# HLK_RM60_KIT_RJ45_V1_1.net
KiCad netlist of a schematic drawn in Altium Designer
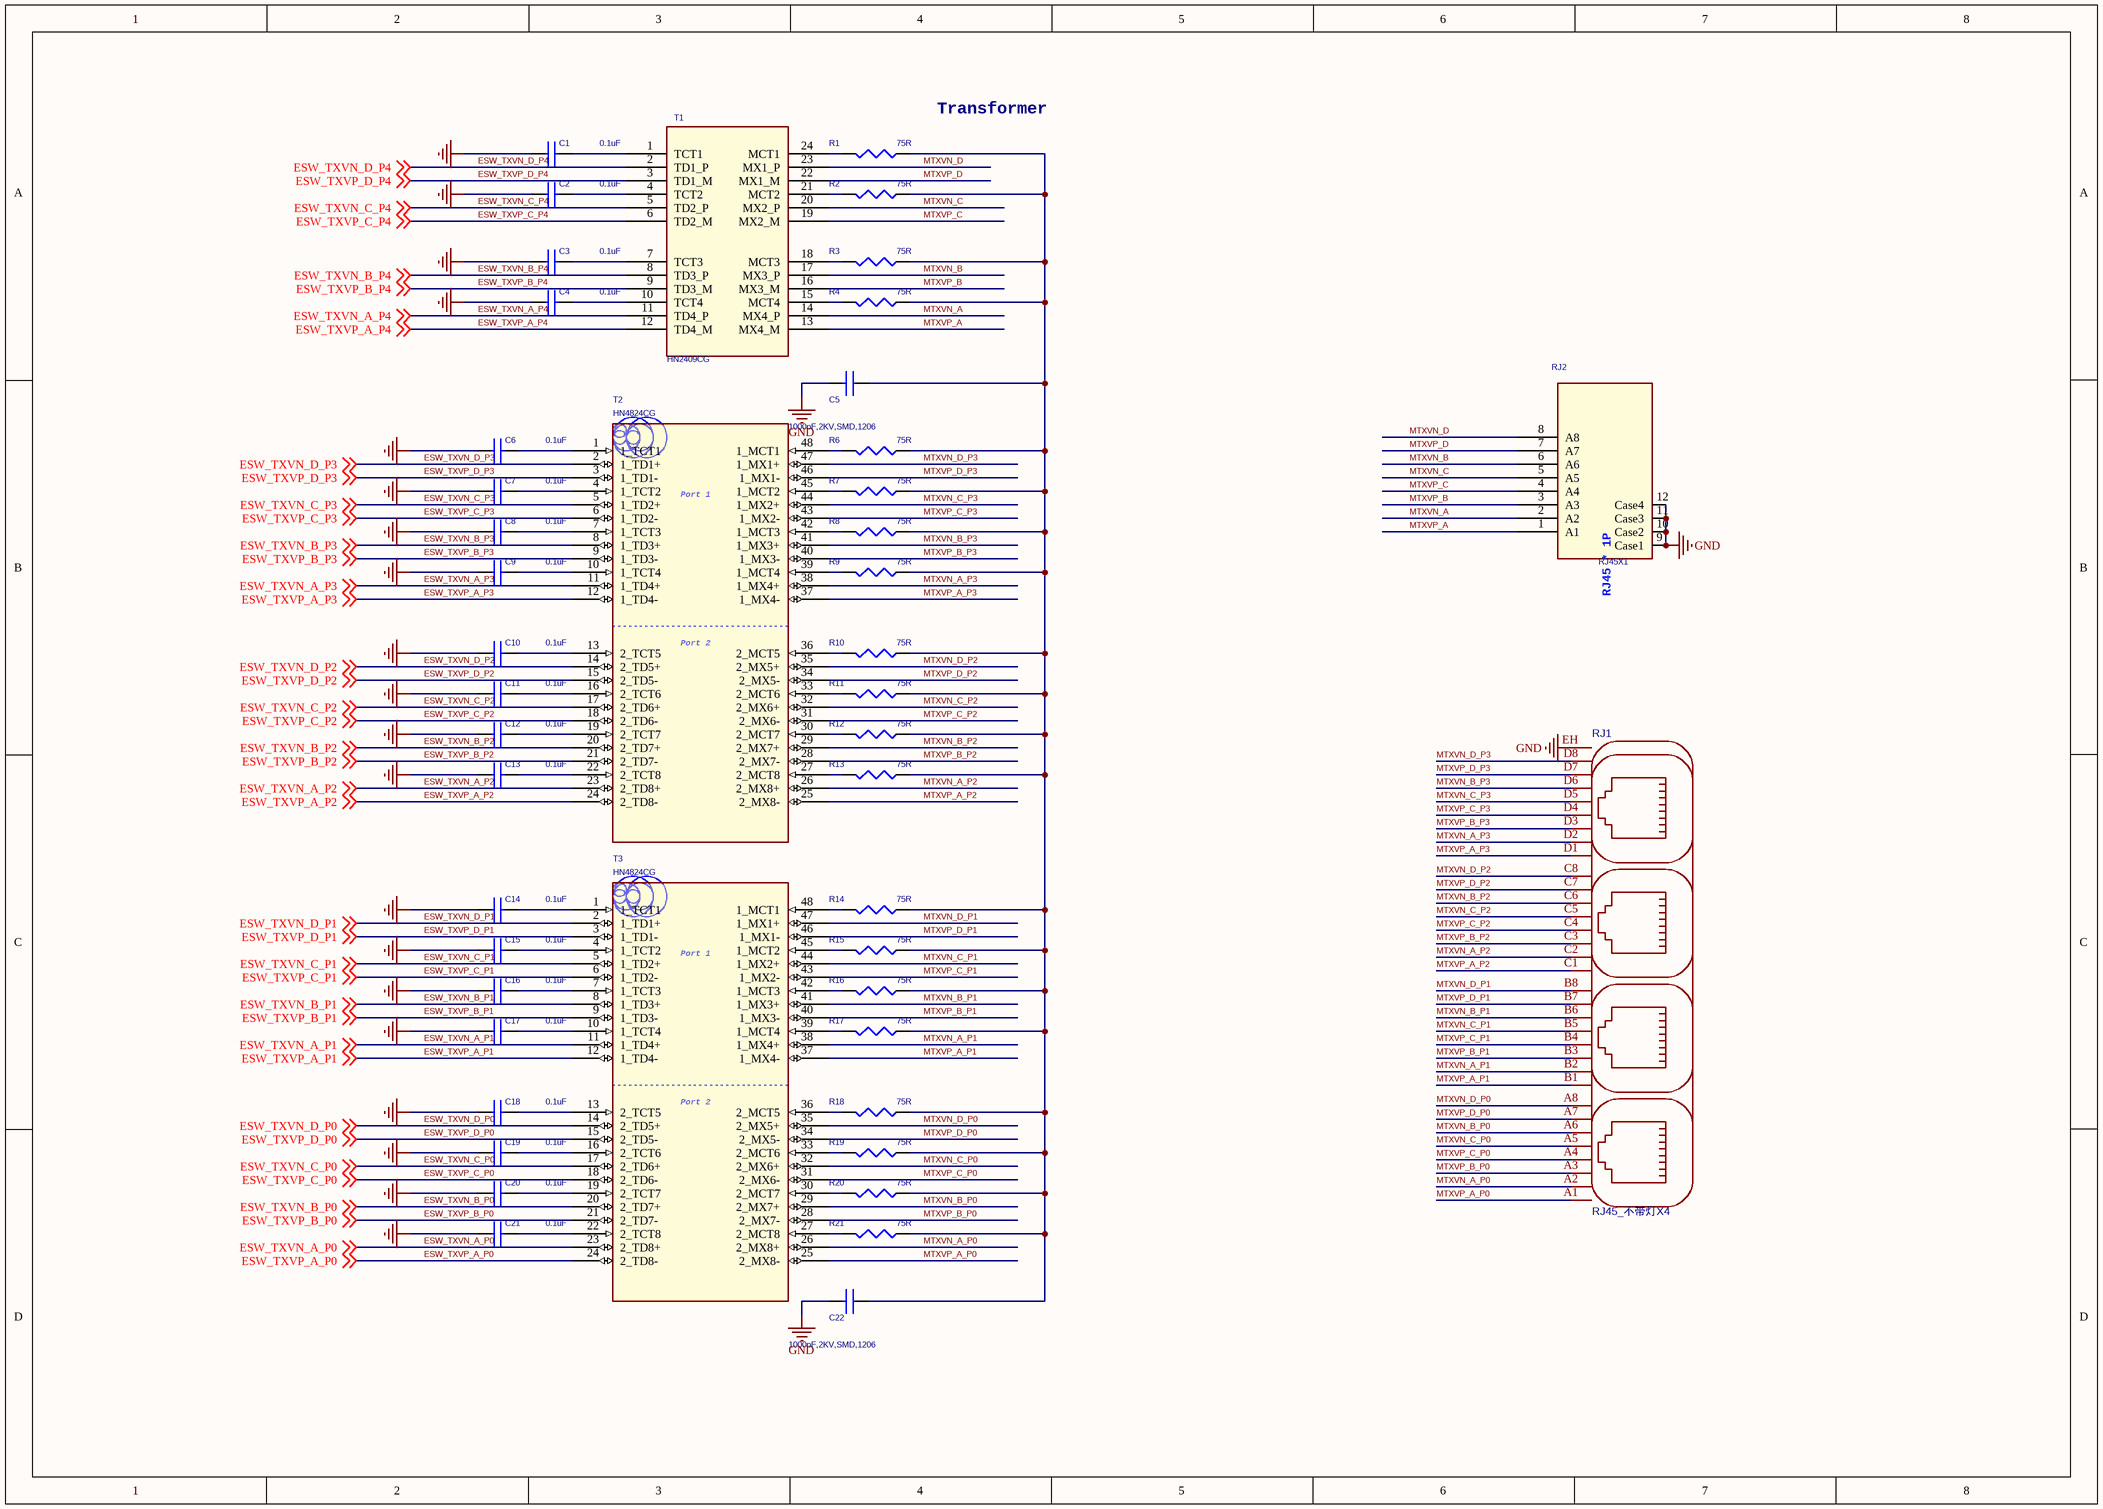
[diagram p0: HLK_RM60_KIT_RJ45_V1.1.SchDoc]

(export (version "E")
  (design (tool "Eeschema 10.0.6"))
  (components
    (comp (ref "C1")
      (value "0.1uF")
      (footprint "C0402")
      (description "Cap, MLCC, 0402, Y5V, 16V")
      (fields
        (field (name "MANUFACTURER") "地穝")
        (field (name "PART NUMBER") "100-110-03400")
        (field (name "BY") "Ralink")
      )
      (libsource (lib "*") (part "0.1UF/25V_+80%-20%_CC_S0603"))
    )
    (comp (ref "C2")
      (value "0.1uF")
      (footprint "C0402")
      (description "Cap, MLCC, 0402, Y5V, 16V")
      (fields
        (field (name "MANUFACTURER") "地穝")
        (field (name "PART NUMBER") "100-110-03400")
        (field (name "BY") "Ralink")
      )
      (libsource (lib "*") (part "0.1UF/25V_+80%-20%_CC_S0603"))
    )
    (comp (ref "C3")
      (value "0.1uF")
      (footprint "C0402")
      (description "Cap, MLCC, 0402, Y5V, 16V")
      (fields
        (field (name "MANUFACTURER") "地穝")
        (field (name "PART NUMBER") "100-110-03400")
        (field (name "BY") "Ralink")
      )
      (libsource (lib "*") (part "0.1UF/25V_+80%-20%_CC_S0603"))
    )
    (comp (ref "C4")
      (value "0.1uF")
      (footprint "C0402")
      (description "Cap, MLCC, 0402, Y5V, 16V")
      (fields
        (field (name "MANUFACTURER") "地穝")
        (field (name "PART NUMBER") "100-110-03400")
        (field (name "BY") "Ralink")
      )
      (libsource (lib "*") (part "0.1UF/25V_+80%-20%_CC_S0603"))
    )
    (comp (ref "C5")
      (value "1000pF,2KV,SMD,1206")
      (footprint "C1206")
      (description "Cap, HighVolt, SMD 1206, 2KV")
      (fields (field (name "MANUFACTURER") "Arcotromics") (field (name "BY") "Ralink"))
      (libsource (lib "*") (part "CAP NP_Dup1"))
    )
    (comp (ref "C6")
      (value "0.1uF")
      (footprint "C0402")
      (description "Cap, MLCC, 0402, Y5V, 16V")
      (fields
        (field (name "PART NUMBER") "100-110-03400")
        (field (name "MANUFACTURER") "地穝")
        (field (name "BY") "Ralink")
      )
      (libsource (lib "*") (part "0.1UF/25V_+80%-20%_CC_S0603"))
    )
    (comp (ref "C7")
      (value "0.1uF")
      (footprint "C0402")
      (description "Cap, MLCC, 0402, Y5V, 16V")
      (fields
        (field (name "PART NUMBER") "100-110-03400")
        (field (name "MANUFACTURER") "地穝")
        (field (name "BY") "Ralink")
      )
      (libsource (lib "*") (part "0.1UF/25V_+80%-20%_CC_S0603"))
    )
    (comp (ref "C8")
      (value "0.1uF")
      (footprint "C0402")
      (description "Cap, MLCC, 0402, Y5V, 16V")
      (fields
        (field (name "PART NUMBER") "100-110-03400")
        (field (name "MANUFACTURER") "地穝")
        (field (name "BY") "Ralink")
      )
      (libsource (lib "*") (part "0.1UF/25V_+80%-20%_CC_S0603"))
    )
    (comp (ref "C9")
      (value "0.1uF")
      (footprint "C0402")
      (description "Cap, MLCC, 0402, Y5V, 16V")
      (fields
        (field (name "PART NUMBER") "100-110-03400")
        (field (name "MANUFACTURER") "地穝")
        (field (name "BY") "Ralink")
      )
      (libsource (lib "*") (part "0.1UF/25V_+80%-20%_CC_S0603"))
    )
    (comp (ref "C10")
      (value "0.1uF")
      (footprint "C0402")
      (description "Cap, MLCC, 0402, Y5V, 16V")
      (fields
        (field (name "MANUFACTURER") "地穝")
        (field (name "PART NUMBER") "100-110-03400")
        (field (name "BY") "Ralink")
      )
      (libsource (lib "*") (part "0.1UF/25V_+80%-20%_CC_S0603"))
    )
    (comp (ref "C11")
      (value "0.1uF")
      (footprint "C0402")
      (description "Cap, MLCC, 0402, Y5V, 16V")
      (fields
        (field (name "MANUFACTURER") "地穝")
        (field (name "PART NUMBER") "100-110-03400")
        (field (name "BY") "Ralink")
      )
      (libsource (lib "*") (part "0.1UF/25V_+80%-20%_CC_S0603"))
    )
    (comp (ref "C12")
      (value "0.1uF")
      (footprint "C0402")
      (description "Cap, MLCC, 0402, Y5V, 16V")
      (fields
        (field (name "MANUFACTURER") "地穝")
        (field (name "PART NUMBER") "100-110-03400")
        (field (name "BY") "Ralink")
      )
      (libsource (lib "*") (part "0.1UF/25V_+80%-20%_CC_S0603"))
    )
    (comp (ref "C13")
      (value "0.1uF")
      (footprint "C0402")
      (description "Cap, MLCC, 0402, Y5V, 16V")
      (fields
        (field (name "MANUFACTURER") "地穝")
        (field (name "PART NUMBER") "100-110-03400")
        (field (name "BY") "Ralink")
      )
      (libsource (lib "*") (part "0.1UF/25V_+80%-20%_CC_S0603"))
    )
    (comp (ref "C14")
      (value "0.1uF")
      (footprint "C0402")
      (description "Cap, MLCC, 0402, Y5V, 16V")
      (fields
        (field (name "MANUFACTURER") "地穝")
        (field (name "PART NUMBER") "100-110-03400")
        (field (name "BY") "Ralink")
      )
      (libsource (lib "*") (part "0.1UF/25V_+80%-20%_CC_S0603"))
    )
    (comp (ref "C15")
      (value "0.1uF")
      (footprint "C0402")
      (description "Cap, MLCC, 0402, Y5V, 16V")
      (fields
        (field (name "MANUFACTURER") "地穝")
        (field (name "PART NUMBER") "100-110-03400")
        (field (name "BY") "Ralink")
      )
      (libsource (lib "*") (part "0.1UF/25V_+80%-20%_CC_S0603"))
    )
    (comp (ref "C16")
      (value "0.1uF")
      (footprint "C0402")
      (description "Cap, MLCC, 0402, Y5V, 16V")
      (fields
        (field (name "PART NUMBER") "100-110-03400")
        (field (name "MANUFACTURER") "地穝")
        (field (name "BY") "Ralink")
      )
      (libsource (lib "*") (part "0.1UF/25V_+80%-20%_CC_S0603"))
    )
    (comp (ref "C17")
      (value "0.1uF")
      (footprint "C0402")
      (description "Cap, MLCC, 0402, Y5V, 16V")
      (fields
        (field (name "PART NUMBER") "100-110-03400")
        (field (name "MANUFACTURER") "地穝")
        (field (name "BY") "Ralink")
      )
      (libsource (lib "*") (part "0.1UF/25V_+80%-20%_CC_S0603"))
    )
    (comp (ref "C18")
      (value "0.1uF")
      (footprint "C0402")
      (description "Cap, MLCC, 0402, Y5V, 16V")
      (fields
        (field (name "MANUFACTURER") "地穝")
        (field (name "PART NUMBER") "100-110-03400")
        (field (name "BY") "Ralink")
      )
      (libsource (lib "*") (part "0.1UF/25V_+80%-20%_CC_S0603"))
    )
    (comp (ref "C19")
      (value "0.1uF")
      (footprint "C0402")
      (description "Cap, MLCC, 0402, Y5V, 16V")
      (fields
        (field (name "MANUFACTURER") "地穝")
        (field (name "PART NUMBER") "100-110-03400")
        (field (name "BY") "Ralink")
      )
      (libsource (lib "*") (part "0.1UF/25V_+80%-20%_CC_S0603"))
    )
    (comp (ref "C20")
      (value "0.1uF")
      (footprint "C0402")
      (description "Cap, MLCC, 0402, Y5V, 16V")
      (fields
        (field (name "PART NUMBER") "100-110-03400")
        (field (name "MANUFACTURER") "地穝")
        (field (name "BY") "Ralink")
      )
      (libsource (lib "*") (part "0.1UF/25V_+80%-20%_CC_S0603"))
    )
    (comp (ref "C21")
      (value "0.1uF")
      (footprint "C0402")
      (description "Cap, MLCC, 0402, Y5V, 16V")
      (fields
        (field (name "PART NUMBER") "100-110-03400")
        (field (name "MANUFACTURER") "地穝")
        (field (name "BY") "Ralink")
      )
      (libsource (lib "*") (part "0.1UF/25V_+80%-20%_CC_S0603"))
    )
    (comp (ref "C22")
      (value "1000pF,2KV,SMD,1206")
      (footprint "C1206")
      (description "Cap, HighVolt, SMD 1206, 2KV")
      (fields (field (name "MANUFACTURER") "Arcotromics") (field (name "BY") "Ralink"))
      (libsource (lib "*") (part "CAP NP_Dup1"))
    )
    (comp (ref "R1")
      (value "75R")
      (footprint "R0402")
      (description "Resistor, 0402, 5%")
      (fields
        (field (name "MANUFACTURER") "驾м")
        (field (name "PART NUMBER") "110-110-03300")
        (field (name "BY") "Ralink")
      )
      (libsource (lib "*") (part "R75_1%_S0603"))
    )
    (comp (ref "R2")
      (value "75R")
      (footprint "R0402")
      (description "Resistor, 0402, 5%")
      (fields
        (field (name "MANUFACTURER") "驾м")
        (field (name "PART NUMBER") "110-110-03300")
        (field (name "BY") "Ralink")
      )
      (libsource (lib "*") (part "R75_1%_S0603"))
    )
    (comp (ref "R3")
      (value "75R")
      (footprint "R0402")
      (description "Resistor, 0402, 5%")
      (fields
        (field (name "MANUFACTURER") "驾м")
        (field (name "PART NUMBER") "110-110-03300")
        (field (name "BY") "Ralink")
      )
      (libsource (lib "*") (part "R75_1%_S0603"))
    )
    (comp (ref "R4")
      (value "75R")
      (footprint "R0402")
      (description "Resistor, 0402, 5%")
      (fields
        (field (name "PART NUMBER") "110-110-03300")
        (field (name "MANUFACTURER") "驾м")
        (field (name "BY") "Ralink")
      )
      (libsource (lib "*") (part "R75_1%_S0603"))
    )
    (comp (ref "R6")
      (value "75R")
      (footprint "R0402")
      (description "Resistor, SMD 0402, 5%")
      (fields
        (field (name "MANUFACTURER") "驾м")
        (field (name "PART NUMBER") "110-110-03300")
        (field (name "BY") "Ralink")
      )
      (libsource (lib "*") (part "R75_1%_S0603"))
    )
    (comp (ref "R7")
      (value "75R")
      (footprint "R0402")
      (description "Resistor, SMD 0402, 5%")
      (fields
        (field (name "PART NUMBER") "110-110-03300")
        (field (name "MANUFACTURER") "驾м")
        (field (name "BY") "Ralink")
      )
      (libsource (lib "*") (part "R75_1%_S0603"))
    )
    (comp (ref "R8")
      (value "75R")
      (footprint "R0402")
      (description "Resistor, SMD 0402, 5%")
      (fields
        (field (name "PART NUMBER") "110-110-03300")
        (field (name "MANUFACTURER") "驾м")
        (field (name "BY") "Ralink")
      )
      (libsource (lib "*") (part "R75_1%_S0603"))
    )
    (comp (ref "R9")
      (value "75R")
      (footprint "R0402")
      (description "Resistor, SMD 0402, 5%")
      (fields
        (field (name "MANUFACTURER") "驾м")
        (field (name "PART NUMBER") "110-110-03300")
        (field (name "BY") "Ralink")
      )
      (libsource (lib "*") (part "R75_1%_S0603"))
    )
    (comp (ref "R10")
      (value "75R")
      (footprint "R0402")
      (description "Resistor, SMD 0402, 5%")
      (fields
        (field (name "PART NUMBER") "110-110-03300")
        (field (name "MANUFACTURER") "驾м")
        (field (name "BY") "Ralink")
      )
      (libsource (lib "*") (part "R75_1%_S0603"))
    )
    (comp (ref "R11")
      (value "75R")
      (footprint "R0402")
      (description "Resistor, SMD 0402, 5%")
      (fields
        (field (name "PART NUMBER") "110-110-03300")
        (field (name "MANUFACTURER") "驾м")
        (field (name "BY") "Ralink")
      )
      (libsource (lib "*") (part "R75_1%_S0603"))
    )
    (comp (ref "R12")
      (value "75R")
      (footprint "R0402")
      (description "Resistor, SMD 0402, 5%")
      (fields
        (field (name "MANUFACTURER") "驾м")
        (field (name "PART NUMBER") "110-110-03300")
        (field (name "BY") "Ralink")
      )
      (libsource (lib "*") (part "R75_1%_S0603"))
    )
    (comp (ref "R13")
      (value "75R")
      (footprint "R0402")
      (description "Resistor, SMD 0402, 5%")
      (fields
        (field (name "PART NUMBER") "110-110-03300")
        (field (name "MANUFACTURER") "驾м")
        (field (name "BY") "Ralink")
      )
      (libsource (lib "*") (part "R75_1%_S0603"))
    )
    (comp (ref "R14")
      (value "75R")
      (footprint "R0402")
      (description "Resistor, SMD 0402, 5%")
      (fields
        (field (name "PART NUMBER") "110-110-03300")
        (field (name "MANUFACTURER") "驾м")
        (field (name "BY") "Ralink")
      )
      (libsource (lib "*") (part "R75_1%_S0603"))
    )
    (comp (ref "R15")
      (value "75R")
      (footprint "R0402")
      (description "Resistor, SMD 0402, 5%")
      (fields
        (field (name "PART NUMBER") "110-110-03300")
        (field (name "MANUFACTURER") "驾м")
        (field (name "BY") "Ralink")
      )
      (libsource (lib "*") (part "R75_1%_S0603"))
    )
    (comp (ref "R16")
      (value "75R")
      (footprint "R0402")
      (description "Resistor, SMD 0402, 5%")
      (fields
        (field (name "PART NUMBER") "110-110-03300")
        (field (name "MANUFACTURER") "驾м")
        (field (name "BY") "Ralink")
      )
      (libsource (lib "*") (part "R75_1%_S0603"))
    )
    (comp (ref "R17")
      (value "75R")
      (footprint "R0402")
      (description "Resistor, SMD 0402, 5%")
      (fields
        (field (name "MANUFACTURER") "驾м")
        (field (name "PART NUMBER") "110-110-03300")
        (field (name "BY") "Ralink")
      )
      (libsource (lib "*") (part "R75_1%_S0603"))
    )
    (comp (ref "R18")
      (value "75R")
      (footprint "R0402")
      (description "Resistor, SMD 0402, 5%")
      (fields
        (field (name "MANUFACTURER") "驾м")
        (field (name "PART NUMBER") "110-110-03300")
        (field (name "BY") "Ralink")
      )
      (libsource (lib "*") (part "R75_1%_S0603"))
    )
    (comp (ref "R19")
      (value "75R")
      (footprint "R0402")
      (description "Resistor, SMD 0402, 5%")
      (fields
        (field (name "MANUFACTURER") "驾м")
        (field (name "PART NUMBER") "110-110-03300")
        (field (name "BY") "Ralink")
      )
      (libsource (lib "*") (part "R75_1%_S0603"))
    )
    (comp (ref "R20")
      (value "75R")
      (footprint "R0402")
      (description "Resistor, SMD 0402, 5%")
      (fields
        (field (name "PART NUMBER") "110-110-03300")
        (field (name "MANUFACTURER") "驾м")
        (field (name "BY") "Ralink")
      )
      (libsource (lib "*") (part "R75_1%_S0603"))
    )
    (comp (ref "R21")
      (value "75R")
      (footprint "R0402")
      (description "Resistor, SMD 0402, 5%")
      (fields
        (field (name "MANUFACTURER") "驾м")
        (field (name "PART NUMBER") "110-110-03300")
        (field (name "BY") "Ralink")
      )
      (libsource (lib "*") (part "R75_1%_S0603"))
    )
    (comp (ref "RJ1")
      (value "RJ45_不带灯X4")
      (footprint "RJ45_网口不带灯X4")
      (fields
        (field (name "BOM_SUPPLIER PART") "C77852")
        (field (name "BOM_MANUFACTURER PART") "DS1129-02-S80BP")
        (field (name "SUBPART_NO") "3")
      )
      (libsource (lib "MY SCHLIB") (part "RJ45_不带灯X4"))
    )
    (comp (ref "RJ2")
      (value "RJ45X1")
      (footprint "RJ45_网口不带灯X1")
      (fields
        (field (name "MANUFACTURER") "救┹")
        (field (name "MANUFACTURER'S PART NUMBER") "PJ-A1-BXBH-FDNNN-1")
        (field (name "PART NUMBER") "214411*12311105")
      )
      (libsource (lib "*") (part "RJ45X1_4"))
    )
    (comp (ref "T1")
      (value "HN2409CG")
      (footprint "TRANSFORMER/24P/SMD/HN2429CG")
      (libsource (lib "*") (part "FT20-252B_2"))
    )
    (comp (ref "T2")
      (value "HN4824CG")
      (footprint "TRANSFORMER/48P/SMD/GS5014LF")
      (libsource (lib "*") (part "XMER 2P G2PM109N"))
    )
    (comp (ref "T3")
      (value "HN4824CG")
      (footprint "TRANSFORMER/48P/SMD/GS5014LF")
      (libsource (lib "*") (part "XMER 2P G2PM109N"))
    )
  )
  (nets
    (net (code "1") (name "/MTXVN_A") (class "Default")
      (node (ref "RJ2") (pin "2") (pinfunction "A2_2") (pintype "passive"))
      (node (ref "T1") (pin "14") (pinfunction "MX4_P_14") (pintype "passive"))
    )
    (net (code "2") (name "/MTXVN_A_P0") (class "Default")
      (node (ref "RJ1") (pin "A2") (pinfunction "A2_A2") (pintype "passive"))
      (node (ref "T3") (pin "26") (pinfunction "2_MX8+_26") (pintype "bidirectional"))
    )
    (net (code "3") (name "/MTXVN_A_P1") (class "Default")
      (node (ref "RJ1") (pin "B2") (pinfunction "B2_B2") (pintype "passive"))
      (node (ref "T3") (pin "38") (pinfunction "1_MX4+_38") (pintype "bidirectional"))
    )
    (net (code "4") (name "/MTXVN_A_P2") (class "Default")
      (node (ref "RJ1") (pin "C2") (pinfunction "C2_C2") (pintype "passive"))
      (node (ref "T2") (pin "26") (pinfunction "2_MX8+_26") (pintype "bidirectional"))
    )
    (net (code "5") (name "/MTXVN_A_P3") (class "Default")
      (node (ref "RJ1") (pin "D2") (pinfunction "D2_D2") (pintype "passive"))
      (node (ref "T2") (pin "38") (pinfunction "1_MX4+_38") (pintype "bidirectional"))
    )
    (net (code "6") (name "/MTXVN_B") (class "Default")
      (node (ref "RJ2") (pin "6") (pinfunction "A6_6") (pintype "passive"))
      (node (ref "T1") (pin "17") (pinfunction "MX3_P_17") (pintype "passive"))
    )
    (net (code "7") (name "/MTXVN_B_P0") (class "Default")
      (node (ref "RJ1") (pin "A6") (pinfunction "A6_A6") (pintype "passive"))
      (node (ref "T3") (pin "29") (pinfunction "2_MX7+_29") (pintype "bidirectional"))
    )
    (net (code "8") (name "/MTXVN_B_P1") (class "Default")
      (node (ref "RJ1") (pin "B6") (pinfunction "B6_B6") (pintype "passive"))
      (node (ref "T3") (pin "41") (pinfunction "1_MX3+_41") (pintype "bidirectional"))
    )
    (net (code "9") (name "/MTXVN_B_P2") (class "Default")
      (node (ref "RJ1") (pin "C6") (pinfunction "C6_C6") (pintype "passive"))
      (node (ref "T2") (pin "29") (pinfunction "2_MX7+_29") (pintype "bidirectional"))
    )
    (net (code "10") (name "/MTXVN_B_P3") (class "Default")
      (node (ref "RJ1") (pin "D6") (pinfunction "D6_D6") (pintype "passive"))
      (node (ref "T2") (pin "41") (pinfunction "1_MX3+_41") (pintype "bidirectional"))
    )
    (net (code "11") (name "/MTXVN_C") (class "Default")
      (node (ref "RJ2") (pin "5") (pinfunction "A5_5") (pintype "passive"))
      (node (ref "T1") (pin "20") (pinfunction "MX2_P_20") (pintype "passive"))
    )
    (net (code "12") (name "/MTXVN_C_P0") (class "Default")
      (node (ref "RJ1") (pin "A5") (pinfunction "A5_A5") (pintype "passive"))
      (node (ref "T3") (pin "32") (pinfunction "2_MX6+_32") (pintype "bidirectional"))
    )
    (net (code "13") (name "/MTXVN_C_P1") (class "Default")
      (node (ref "RJ1") (pin "B5") (pinfunction "B5_B5") (pintype "passive"))
      (node (ref "T3") (pin "44") (pinfunction "1_MX2+_44") (pintype "bidirectional"))
    )
    (net (code "14") (name "/MTXVN_C_P2") (class "Default")
      (node (ref "RJ1") (pin "C5") (pinfunction "C5_C5") (pintype "passive"))
      (node (ref "T2") (pin "32") (pinfunction "2_MX6+_32") (pintype "bidirectional"))
    )
    (net (code "15") (name "/MTXVN_C_P3") (class "Default")
      (node (ref "RJ1") (pin "D5") (pinfunction "D5_D5") (pintype "passive"))
      (node (ref "T2") (pin "44") (pinfunction "1_MX2+_44") (pintype "bidirectional"))
    )
    (net (code "16") (name "/MTXVN_D") (class "Default")
      (node (ref "RJ2") (pin "8") (pinfunction "A8_8") (pintype "passive"))
      (node (ref "T1") (pin "23") (pinfunction "MX1_P_23") (pintype "passive"))
    )
    (net (code "17") (name "/MTXVN_D_P0") (class "Default")
      (node (ref "RJ1") (pin "A8") (pinfunction "A8_A8") (pintype "passive"))
      (node (ref "T3") (pin "35") (pinfunction "2_MX5+_35") (pintype "bidirectional"))
    )
    (net (code "18") (name "/MTXVN_D_P1") (class "Default")
      (node (ref "RJ1") (pin "B8") (pinfunction "B8_B8") (pintype "passive"))
      (node (ref "T3") (pin "47") (pinfunction "1_MX1+_47") (pintype "bidirectional"))
    )
    (net (code "19") (name "/MTXVN_D_P2") (class "Default")
      (node (ref "RJ1") (pin "C8") (pinfunction "C8_C8") (pintype "passive"))
      (node (ref "T2") (pin "35") (pinfunction "2_MX5+_35") (pintype "bidirectional"))
    )
    (net (code "20") (name "/MTXVN_D_P3") (class "Default")
      (node (ref "RJ1") (pin "D8") (pinfunction "D8_D8") (pintype "passive"))
      (node (ref "T2") (pin "47") (pinfunction "1_MX1+_47") (pintype "bidirectional"))
    )
    (net (code "21") (name "/MTXVP_A") (class "Default")
      (node (ref "RJ2") (pin "1") (pinfunction "A1_1") (pintype "passive"))
      (node (ref "T1") (pin "13") (pinfunction "MX4_M_13") (pintype "passive"))
    )
    (net (code "22") (name "/MTXVP_A_P0") (class "Default")
      (node (ref "RJ1") (pin "A1") (pinfunction "A1_A1") (pintype "passive"))
      (node (ref "T3") (pin "25") (pinfunction "2_MX8-_25") (pintype "bidirectional"))
    )
    (net (code "23") (name "/MTXVP_A_P1") (class "Default")
      (node (ref "RJ1") (pin "B1") (pinfunction "B1_B1") (pintype "passive"))
      (node (ref "T3") (pin "37") (pinfunction "1_MX4-_37") (pintype "bidirectional"))
    )
    (net (code "24") (name "/MTXVP_A_P2") (class "Default")
      (node (ref "RJ1") (pin "C1") (pinfunction "C1_C1") (pintype "passive"))
      (node (ref "T2") (pin "25") (pinfunction "2_MX8-_25") (pintype "bidirectional"))
    )
    (net (code "25") (name "/MTXVP_A_P3") (class "Default")
      (node (ref "RJ1") (pin "D1") (pinfunction "D1_D1") (pintype "passive"))
      (node (ref "T2") (pin "37") (pinfunction "1_MX4-_37") (pintype "bidirectional"))
    )
    (net (code "26") (name "/MTXVP_B") (class "Default")
      (node (ref "RJ2") (pin "3") (pinfunction "A3_3") (pintype "passive"))
      (node (ref "T1") (pin "16") (pinfunction "MX3_M_16") (pintype "passive"))
    )
    (net (code "27") (name "/MTXVP_B_P0") (class "Default")
      (node (ref "RJ1") (pin "A3") (pinfunction "A3_A3") (pintype "passive"))
      (node (ref "T3") (pin "28") (pinfunction "2_MX7-_28") (pintype "bidirectional"))
    )
    (net (code "28") (name "/MTXVP_B_P1") (class "Default")
      (node (ref "RJ1") (pin "B3") (pinfunction "B3_B3") (pintype "passive"))
      (node (ref "T3") (pin "40") (pinfunction "1_MX3-_40") (pintype "bidirectional"))
    )
    (net (code "29") (name "/MTXVP_B_P2") (class "Default")
      (node (ref "RJ1") (pin "C3") (pinfunction "C3_C3") (pintype "passive"))
      (node (ref "T2") (pin "28") (pinfunction "2_MX7-_28") (pintype "bidirectional"))
    )
    (net (code "30") (name "/MTXVP_B_P3") (class "Default")
      (node (ref "RJ1") (pin "D3") (pinfunction "D3_D3") (pintype "passive"))
      (node (ref "T2") (pin "40") (pinfunction "1_MX3-_40") (pintype "bidirectional"))
    )
    (net (code "31") (name "/MTXVP_C") (class "Default")
      (node (ref "RJ2") (pin "4") (pinfunction "A4_4") (pintype "passive"))
      (node (ref "T1") (pin "19") (pinfunction "MX2_M_19") (pintype "passive"))
    )
    (net (code "32") (name "/MTXVP_C_P0") (class "Default")
      (node (ref "RJ1") (pin "A4") (pinfunction "A4_A4") (pintype "passive"))
      (node (ref "T3") (pin "31") (pinfunction "2_MX6-_31") (pintype "bidirectional"))
    )
    (net (code "33") (name "/MTXVP_C_P1") (class "Default")
      (node (ref "RJ1") (pin "B4") (pinfunction "B4_B4") (pintype "passive"))
      (node (ref "T3") (pin "43") (pinfunction "1_MX2-_43") (pintype "bidirectional"))
    )
    (net (code "34") (name "/MTXVP_C_P2") (class "Default")
      (node (ref "RJ1") (pin "C4") (pinfunction "C4_C4") (pintype "passive"))
      (node (ref "T2") (pin "31") (pinfunction "2_MX6-_31") (pintype "bidirectional"))
    )
    (net (code "35") (name "/MTXVP_C_P3") (class "Default")
      (node (ref "RJ1") (pin "D4") (pinfunction "D4_D4") (pintype "passive"))
      (node (ref "T2") (pin "43") (pinfunction "1_MX2-_43") (pintype "bidirectional"))
    )
    (net (code "36") (name "/MTXVP_D") (class "Default")
      (node (ref "RJ2") (pin "7") (pinfunction "A7_7") (pintype "passive"))
      (node (ref "T1") (pin "22") (pinfunction "MX1_M_22") (pintype "passive"))
    )
    (net (code "37") (name "/MTXVP_D_P0") (class "Default")
      (node (ref "RJ1") (pin "A7") (pinfunction "A7_A7") (pintype "passive"))
      (node (ref "T3") (pin "34") (pinfunction "2_MX5-_34") (pintype "bidirectional"))
    )
    (net (code "38") (name "/MTXVP_D_P1") (class "Default")
      (node (ref "RJ1") (pin "B7") (pinfunction "B7_B7") (pintype "passive"))
      (node (ref "T3") (pin "46") (pinfunction "1_MX1-_46") (pintype "bidirectional"))
    )
    (net (code "39") (name "/MTXVP_D_P2") (class "Default")
      (node (ref "RJ1") (pin "C7") (pinfunction "C7_C7") (pintype "passive"))
      (node (ref "T2") (pin "34") (pinfunction "2_MX5-_34") (pintype "bidirectional"))
    )
    (net (code "40") (name "/MTXVP_D_P3") (class "Default")
      (node (ref "RJ1") (pin "D7") (pinfunction "D7_D7") (pintype "passive"))
      (node (ref "T2") (pin "46") (pinfunction "1_MX1-_46") (pintype "bidirectional"))
    )
    (net (code "41") (name "ESW_TXVN_A_P0") (class "Default")
      (node (ref "T3") (pin "23") (pinfunction "2_TD8+_23") (pintype "bidirectional"))
    )
    (net (code "42") (name "ESW_TXVN_A_P1") (class "Default")
      (node (ref "T3") (pin "11") (pinfunction "1_TD4+_11") (pintype "bidirectional"))
    )
    (net (code "43") (name "ESW_TXVN_A_P2") (class "Default")
      (node (ref "T2") (pin "23") (pinfunction "2_TD8+_23") (pintype "bidirectional"))
    )
    (net (code "44") (name "ESW_TXVN_A_P3") (class "Default")
      (node (ref "T2") (pin "11") (pinfunction "1_TD4+_11") (pintype "bidirectional"))
    )
    (net (code "45") (name "ESW_TXVN_A_P4") (class "Default")
      (node (ref "T1") (pin "11") (pinfunction "TD4_P_11") (pintype "passive"))
    )
    (net (code "46") (name "ESW_TXVN_B_P0") (class "Default")
      (node (ref "T3") (pin "20") (pinfunction "2_TD7+_20") (pintype "bidirectional"))
    )
    (net (code "47") (name "ESW_TXVN_B_P1") (class "Default")
      (node (ref "T3") (pin "8") (pinfunction "1_TD3+_8") (pintype "bidirectional"))
    )
    (net (code "48") (name "ESW_TXVN_B_P2") (class "Default")
      (node (ref "T2") (pin "20") (pinfunction "2_TD7+_20") (pintype "bidirectional"))
    )
    (net (code "49") (name "ESW_TXVN_B_P3") (class "Default")
      (node (ref "T2") (pin "8") (pinfunction "1_TD3+_8") (pintype "bidirectional"))
    )
    (net (code "50") (name "ESW_TXVN_B_P4") (class "Default")
      (node (ref "T1") (pin "8") (pinfunction "TD3_P_8") (pintype "passive"))
    )
    (net (code "51") (name "ESW_TXVN_C_P0") (class "Default")
      (node (ref "T3") (pin "17") (pinfunction "2_TD6+_17") (pintype "bidirectional"))
    )
    (net (code "52") (name "ESW_TXVN_C_P1") (class "Default")
      (node (ref "T3") (pin "5") (pinfunction "1_TD2+_5") (pintype "bidirectional"))
    )
    (net (code "53") (name "ESW_TXVN_C_P2") (class "Default")
      (node (ref "T2") (pin "17") (pinfunction "2_TD6+_17") (pintype "bidirectional"))
    )
    (net (code "54") (name "ESW_TXVN_C_P3") (class "Default")
      (node (ref "T2") (pin "5") (pinfunction "1_TD2+_5") (pintype "bidirectional"))
    )
    (net (code "55") (name "ESW_TXVN_C_P4") (class "Default")
      (node (ref "T1") (pin "5") (pinfunction "TD2_P_5") (pintype "passive"))
    )
    (net (code "56") (name "ESW_TXVN_D_P0") (class "Default")
      (node (ref "T3") (pin "14") (pinfunction "2_TD5+_14") (pintype "bidirectional"))
    )
    (net (code "57") (name "ESW_TXVN_D_P1") (class "Default")
      (node (ref "T3") (pin "2") (pinfunction "1_TD1+_2") (pintype "bidirectional"))
    )
    (net (code "58") (name "ESW_TXVN_D_P2") (class "Default")
      (node (ref "T2") (pin "14") (pinfunction "2_TD5+_14") (pintype "bidirectional"))
    )
    (net (code "59") (name "ESW_TXVN_D_P3") (class "Default")
      (node (ref "T2") (pin "2") (pinfunction "1_TD1+_2") (pintype "bidirectional"))
    )
    (net (code "60") (name "ESW_TXVN_D_P4") (class "Default")
      (node (ref "T1") (pin "2") (pinfunction "TD1_P_2") (pintype "passive"))
    )
    (net (code "61") (name "ESW_TXVP_A_P0") (class "Default")
      (node (ref "T3") (pin "24") (pinfunction "2_TD8-_24") (pintype "bidirectional"))
    )
    (net (code "62") (name "ESW_TXVP_A_P1") (class "Default")
      (node (ref "T3") (pin "12") (pinfunction "1_TD4-_12") (pintype "bidirectional"))
    )
    (net (code "63") (name "ESW_TXVP_A_P2") (class "Default")
      (node (ref "T2") (pin "24") (pinfunction "2_TD8-_24") (pintype "bidirectional"))
    )
    (net (code "64") (name "ESW_TXVP_A_P3") (class "Default")
      (node (ref "T2") (pin "12") (pinfunction "1_TD4-_12") (pintype "bidirectional"))
    )
    (net (code "65") (name "ESW_TXVP_A_P4") (class "Default")
      (node (ref "T1") (pin "12") (pinfunction "TD4_M_12") (pintype "passive"))
    )
    (net (code "66") (name "ESW_TXVP_B_P0") (class "Default")
      (node (ref "T3") (pin "21") (pinfunction "2_TD7-_21") (pintype "bidirectional"))
    )
    (net (code "67") (name "ESW_TXVP_B_P1") (class "Default")
      (node (ref "T3") (pin "9") (pinfunction "1_TD3-_9") (pintype "bidirectional"))
    )
    (net (code "68") (name "ESW_TXVP_B_P2") (class "Default")
      (node (ref "T2") (pin "21") (pinfunction "2_TD7-_21") (pintype "bidirectional"))
    )
    (net (code "69") (name "ESW_TXVP_B_P3") (class "Default")
      (node (ref "T2") (pin "9") (pinfunction "1_TD3-_9") (pintype "bidirectional"))
    )
    (net (code "70") (name "ESW_TXVP_B_P4") (class "Default")
      (node (ref "T1") (pin "9") (pinfunction "TD3_M_9") (pintype "passive"))
    )
    (net (code "71") (name "ESW_TXVP_C_P0") (class "Default")
      (node (ref "T3") (pin "18") (pinfunction "2_TD6-_18") (pintype "bidirectional"))
    )
    (net (code "72") (name "ESW_TXVP_C_P1") (class "Default")
      (node (ref "T3") (pin "6") (pinfunction "1_TD2-_6") (pintype "bidirectional"))
    )
    (net (code "73") (name "ESW_TXVP_C_P2") (class "Default")
      (node (ref "T2") (pin "18") (pinfunction "2_TD6-_18") (pintype "bidirectional"))
    )
    (net (code "74") (name "ESW_TXVP_C_P3") (class "Default")
      (node (ref "T2") (pin "6") (pinfunction "1_TD2-_6") (pintype "bidirectional"))
    )
    (net (code "75") (name "ESW_TXVP_C_P4") (class "Default")
      (node (ref "T1") (pin "6") (pinfunction "TD2_M_6") (pintype "passive"))
    )
    (net (code "76") (name "ESW_TXVP_D_P0") (class "Default")
      (node (ref "T3") (pin "15") (pinfunction "2_TD5-_15") (pintype "bidirectional"))
    )
    (net (code "77") (name "ESW_TXVP_D_P1") (class "Default")
      (node (ref "T3") (pin "3") (pinfunction "1_TD1-_3") (pintype "bidirectional"))
    )
    (net (code "78") (name "ESW_TXVP_D_P2") (class "Default")
      (node (ref "T2") (pin "15") (pinfunction "2_TD5-_15") (pintype "bidirectional"))
    )
    (net (code "79") (name "ESW_TXVP_D_P3") (class "Default")
      (node (ref "T2") (pin "3") (pinfunction "1_TD1-_3") (pintype "bidirectional"))
    )
    (net (code "80") (name "ESW_TXVP_D_P4") (class "Default")
      (node (ref "T1") (pin "3") (pinfunction "TD1_M_3") (pintype "passive"))
    )
    (net (code "81") (name "GND") (class "Default")
      (node (ref "C1") (pin "1") (pinfunction "1_1") (pintype "passive"))
      (node (ref "C10") (pin "1") (pinfunction "1_1") (pintype "passive"))
      (node (ref "C11") (pin "1") (pinfunction "1_1") (pintype "passive"))
      (node (ref "C12") (pin "1") (pinfunction "1_1") (pintype "passive"))
      (node (ref "C13") (pin "1") (pinfunction "1_1") (pintype "passive"))
      (node (ref "C14") (pin "1") (pinfunction "1_1") (pintype "passive"))
      (node (ref "C15") (pin "1") (pinfunction "1_1") (pintype "passive"))
      (node (ref "C16") (pin "1") (pinfunction "1_1") (pintype "passive"))
      (node (ref "C17") (pin "1") (pinfunction "1_1") (pintype "passive"))
      (node (ref "C18") (pin "1") (pinfunction "1_1") (pintype "passive"))
      (node (ref "C19") (pin "1") (pinfunction "1_1") (pintype "passive"))
      (node (ref "C2") (pin "1") (pinfunction "1_1") (pintype "passive"))
      (node (ref "C20") (pin "1") (pinfunction "1_1") (pintype "passive"))
      (node (ref "C21") (pin "1") (pinfunction "1_1") (pintype "passive"))
      (node (ref "C22") (pin "2") (pinfunction "2_2") (pintype "passive"))
      (node (ref "C3") (pin "1") (pinfunction "1_1") (pintype "passive"))
      (node (ref "C4") (pin "1") (pinfunction "1_1") (pintype "passive"))
      (node (ref "C5") (pin "2") (pinfunction "2_2") (pintype "passive"))
      (node (ref "C6") (pin "1") (pinfunction "1_1") (pintype "passive"))
      (node (ref "C7") (pin "1") (pinfunction "1_1") (pintype "passive"))
      (node (ref "C8") (pin "1") (pinfunction "1_1") (pintype "passive"))
      (node (ref "C9") (pin "1") (pinfunction "1_1") (pintype "passive"))
      (node (ref "RJ1") (pin "EH") (pinfunction "EH_EH") (pintype "passive"))
      (node (ref "RJ2") (pin "10") (pinfunction "Case2_10") (pintype "passive"))
      (node (ref "RJ2") (pin "11") (pinfunction "Case3_11") (pintype "passive"))
      (node (ref "RJ2") (pin "12") (pinfunction "Case4_12") (pintype "passive"))
      (node (ref "RJ2") (pin "9") (pinfunction "Case1_9") (pintype "passive"))
    )
    (net (code "82") (name "Net-(C22-Pad1)") (class "Default")
      (node (ref "C22") (pin "1") (pinfunction "1_1") (pintype "passive"))
      (node (ref "C5") (pin "1") (pinfunction "1_1") (pintype "passive"))
      (node (ref "R1") (pin "1") (pinfunction "1_1") (pintype "passive"))
      (node (ref "R10") (pin "1") (pinfunction "1_1") (pintype "passive"))
      (node (ref "R11") (pin "1") (pinfunction "1_1") (pintype "passive"))
      (node (ref "R12") (pin "1") (pinfunction "1_1") (pintype "passive"))
      (node (ref "R13") (pin "1") (pinfunction "1_1") (pintype "passive"))
      (node (ref "R14") (pin "1") (pinfunction "1_1") (pintype "passive"))
      (node (ref "R15") (pin "1") (pinfunction "1_1") (pintype "passive"))
      (node (ref "R16") (pin "1") (pinfunction "1_1") (pintype "passive"))
      (node (ref "R17") (pin "1") (pinfunction "1_1") (pintype "passive"))
      (node (ref "R18") (pin "1") (pinfunction "1_1") (pintype "passive"))
      (node (ref "R19") (pin "1") (pinfunction "1_1") (pintype "passive"))
      (node (ref "R2") (pin "1") (pinfunction "1_1") (pintype "passive"))
      (node (ref "R20") (pin "1") (pinfunction "1_1") (pintype "passive"))
      (node (ref "R21") (pin "1") (pinfunction "1_1") (pintype "passive"))
      (node (ref "R3") (pin "1") (pinfunction "1_1") (pintype "passive"))
      (node (ref "R4") (pin "1") (pinfunction "1_1") (pintype "passive"))
      (node (ref "R6") (pin "1") (pinfunction "1_1") (pintype "passive"))
      (node (ref "R7") (pin "1") (pinfunction "1_1") (pintype "passive"))
      (node (ref "R8") (pin "1") (pinfunction "1_1") (pintype "passive"))
      (node (ref "R9") (pin "1") (pinfunction "1_1") (pintype "passive"))
    )
    (net (code "83") (name "Net-(T1-MCT1)") (class "Default")
      (node (ref "R1") (pin "2") (pinfunction "2_2") (pintype "passive"))
      (node (ref "T1") (pin "24") (pinfunction "MCT1_24") (pintype "passive"))
    )
    (net (code "84") (name "Net-(T1-MCT2)") (class "Default")
      (node (ref "R2") (pin "2") (pinfunction "2_2") (pintype "passive"))
      (node (ref "T1") (pin "21") (pinfunction "MCT2_21") (pintype "passive"))
    )
    (net (code "85") (name "Net-(T1-MCT3)") (class "Default")
      (node (ref "R3") (pin "2") (pinfunction "2_2") (pintype "passive"))
      (node (ref "T1") (pin "18") (pinfunction "MCT3_18") (pintype "passive"))
    )
    (net (code "86") (name "Net-(T1-MCT4)") (class "Default")
      (node (ref "R4") (pin "2") (pinfunction "2_2") (pintype "passive"))
      (node (ref "T1") (pin "15") (pinfunction "MCT4_15") (pintype "passive"))
    )
    (net (code "87") (name "Net-(T1-TCT1)") (class "Default")
      (node (ref "C1") (pin "2") (pinfunction "2_2") (pintype "passive"))
      (node (ref "T1") (pin "1") (pinfunction "TCT1_1") (pintype "passive"))
    )
    (net (code "88") (name "Net-(T1-TCT2)") (class "Default")
      (node (ref "C2") (pin "2") (pinfunction "2_2") (pintype "passive"))
      (node (ref "T1") (pin "4") (pinfunction "TCT2_4") (pintype "passive"))
    )
    (net (code "89") (name "Net-(T1-TCT3)") (class "Default")
      (node (ref "C3") (pin "2") (pinfunction "2_2") (pintype "passive"))
      (node (ref "T1") (pin "7") (pinfunction "TCT3_7") (pintype "passive"))
    )
    (net (code "90") (name "Net-(T1-TCT4)") (class "Default")
      (node (ref "C4") (pin "2") (pinfunction "2_2") (pintype "passive"))
      (node (ref "T1") (pin "10") (pinfunction "TCT4_10") (pintype "passive"))
    )
    (net (code "91") (name "Net-(T2-1_MCT1)") (class "Default")
      (node (ref "R6") (pin "2") (pinfunction "2_2") (pintype "passive"))
      (node (ref "T2") (pin "48") (pinfunction "1_MCT1_48") (pintype "input"))
    )
    (net (code "92") (name "Net-(T2-1_MCT2)") (class "Default")
      (node (ref "R7") (pin "2") (pinfunction "2_2") (pintype "passive"))
      (node (ref "T2") (pin "45") (pinfunction "1_MCT2_45") (pintype "input"))
    )
    (net (code "93") (name "Net-(T2-1_MCT3)") (class "Default")
      (node (ref "R8") (pin "2") (pinfunction "2_2") (pintype "passive"))
      (node (ref "T2") (pin "42") (pinfunction "1_MCT3_42") (pintype "input"))
    )
    (net (code "94") (name "Net-(T2-1_MCT4)") (class "Default")
      (node (ref "R9") (pin "2") (pinfunction "2_2") (pintype "passive"))
      (node (ref "T2") (pin "39") (pinfunction "1_MCT4_39") (pintype "input"))
    )
    (net (code "95") (name "Net-(T2-1_TCT1)") (class "Default")
      (node (ref "C6") (pin "2") (pinfunction "2_2") (pintype "passive"))
      (node (ref "T2") (pin "1") (pinfunction "1_TCT1_1") (pintype "input"))
    )
    (net (code "96") (name "Net-(T2-1_TCT2)") (class "Default")
      (node (ref "C7") (pin "2") (pinfunction "2_2") (pintype "passive"))
      (node (ref "T2") (pin "4") (pinfunction "1_TCT2_4") (pintype "input"))
    )
    (net (code "97") (name "Net-(T2-1_TCT3)") (class "Default")
      (node (ref "C8") (pin "2") (pinfunction "2_2") (pintype "passive"))
      (node (ref "T2") (pin "7") (pinfunction "1_TCT3_7") (pintype "input"))
    )
    (net (code "98") (name "Net-(T2-1_TCT4)") (class "Default")
      (node (ref "C9") (pin "2") (pinfunction "2_2") (pintype "passive"))
      (node (ref "T2") (pin "10") (pinfunction "1_TCT4_10") (pintype "input"))
    )
    (net (code "99") (name "Net-(T2-2_MCT5)") (class "Default")
      (node (ref "R10") (pin "2") (pinfunction "2_2") (pintype "passive"))
      (node (ref "T2") (pin "36") (pinfunction "2_MCT5_36") (pintype "input"))
    )
    (net (code "100") (name "Net-(T2-2_MCT6)") (class "Default")
      (node (ref "R11") (pin "2") (pinfunction "2_2") (pintype "passive"))
      (node (ref "T2") (pin "33") (pinfunction "2_MCT6_33") (pintype "input"))
    )
    (net (code "101") (name "Net-(T2-2_MCT7)") (class "Default")
      (node (ref "R12") (pin "2") (pinfunction "2_2") (pintype "passive"))
      (node (ref "T2") (pin "30") (pinfunction "2_MCT7_30") (pintype "input"))
    )
    (net (code "102") (name "Net-(T2-2_MCT8)") (class "Default")
      (node (ref "R13") (pin "2") (pinfunction "2_2") (pintype "passive"))
      (node (ref "T2") (pin "27") (pinfunction "2_MCT8_27") (pintype "input"))
    )
    (net (code "103") (name "Net-(T2-2_TCT5)") (class "Default")
      (node (ref "C10") (pin "2") (pinfunction "2_2") (pintype "passive"))
      (node (ref "T2") (pin "13") (pinfunction "2_TCT5_13") (pintype "input"))
    )
    (net (code "104") (name "Net-(T2-2_TCT6)") (class "Default")
      (node (ref "C11") (pin "2") (pinfunction "2_2") (pintype "passive"))
      (node (ref "T2") (pin "16") (pinfunction "2_TCT6_16") (pintype "input"))
    )
    (net (code "105") (name "Net-(T2-2_TCT7)") (class "Default")
      (node (ref "C12") (pin "2") (pinfunction "2_2") (pintype "passive"))
      (node (ref "T2") (pin "19") (pinfunction "2_TCT7_19") (pintype "input"))
    )
    (net (code "106") (name "Net-(T2-2_TCT8)") (class "Default")
      (node (ref "C13") (pin "2") (pinfunction "2_2") (pintype "passive"))
      (node (ref "T2") (pin "22") (pinfunction "2_TCT8_22") (pintype "input"))
    )
    (net (code "107") (name "Net-(T3-1_MCT1)") (class "Default")
      (node (ref "R14") (pin "2") (pinfunction "2_2") (pintype "passive"))
      (node (ref "T3") (pin "48") (pinfunction "1_MCT1_48") (pintype "input"))
    )
    (net (code "108") (name "Net-(T3-1_MCT2)") (class "Default")
      (node (ref "R15") (pin "2") (pinfunction "2_2") (pintype "passive"))
      (node (ref "T3") (pin "45") (pinfunction "1_MCT2_45") (pintype "input"))
    )
    (net (code "109") (name "Net-(T3-1_MCT3)") (class "Default")
      (node (ref "R16") (pin "2") (pinfunction "2_2") (pintype "passive"))
      (node (ref "T3") (pin "42") (pinfunction "1_MCT3_42") (pintype "input"))
    )
    (net (code "110") (name "Net-(T3-1_MCT4)") (class "Default")
      (node (ref "R17") (pin "2") (pinfunction "2_2") (pintype "passive"))
      (node (ref "T3") (pin "39") (pinfunction "1_MCT4_39") (pintype "input"))
    )
    (net (code "111") (name "Net-(T3-1_TCT1)") (class "Default")
      (node (ref "C14") (pin "2") (pinfunction "2_2") (pintype "passive"))
      (node (ref "T3") (pin "1") (pinfunction "1_TCT1_1") (pintype "input"))
    )
    (net (code "112") (name "Net-(T3-1_TCT2)") (class "Default")
      (node (ref "C15") (pin "2") (pinfunction "2_2") (pintype "passive"))
      (node (ref "T3") (pin "4") (pinfunction "1_TCT2_4") (pintype "input"))
    )
    (net (code "113") (name "Net-(T3-1_TCT3)") (class "Default")
      (node (ref "C16") (pin "2") (pinfunction "2_2") (pintype "passive"))
      (node (ref "T3") (pin "7") (pinfunction "1_TCT3_7") (pintype "input"))
    )
    (net (code "114") (name "Net-(T3-1_TCT4)") (class "Default")
      (node (ref "C17") (pin "2") (pinfunction "2_2") (pintype "passive"))
      (node (ref "T3") (pin "10") (pinfunction "1_TCT4_10") (pintype "input"))
    )
    (net (code "115") (name "Net-(T3-2_MCT5)") (class "Default")
      (node (ref "R18") (pin "2") (pinfunction "2_2") (pintype "passive"))
      (node (ref "T3") (pin "36") (pinfunction "2_MCT5_36") (pintype "input"))
    )
    (net (code "116") (name "Net-(T3-2_MCT6)") (class "Default")
      (node (ref "R19") (pin "2") (pinfunction "2_2") (pintype "passive"))
      (node (ref "T3") (pin "33") (pinfunction "2_MCT6_33") (pintype "input"))
    )
    (net (code "117") (name "Net-(T3-2_MCT7)") (class "Default")
      (node (ref "R20") (pin "2") (pinfunction "2_2") (pintype "passive"))
      (node (ref "T3") (pin "30") (pinfunction "2_MCT7_30") (pintype "input"))
    )
    (net (code "118") (name "Net-(T3-2_MCT8)") (class "Default")
      (node (ref "R21") (pin "2") (pinfunction "2_2") (pintype "passive"))
      (node (ref "T3") (pin "27") (pinfunction "2_MCT8_27") (pintype "input"))
    )
    (net (code "119") (name "Net-(T3-2_TCT5)") (class "Default")
      (node (ref "C18") (pin "2") (pinfunction "2_2") (pintype "passive"))
      (node (ref "T3") (pin "13") (pinfunction "2_TCT5_13") (pintype "input"))
    )
    (net (code "120") (name "Net-(T3-2_TCT6)") (class "Default")
      (node (ref "C19") (pin "2") (pinfunction "2_2") (pintype "passive"))
      (node (ref "T3") (pin "16") (pinfunction "2_TCT6_16") (pintype "input"))
    )
    (net (code "121") (name "Net-(T3-2_TCT7)") (class "Default")
      (node (ref "C20") (pin "2") (pinfunction "2_2") (pintype "passive"))
      (node (ref "T3") (pin "19") (pinfunction "2_TCT7_19") (pintype "input"))
    )
    (net (code "122") (name "Net-(T3-2_TCT8)") (class "Default")
      (node (ref "C21") (pin "2") (pinfunction "2_2") (pintype "passive"))
      (node (ref "T3") (pin "22") (pinfunction "2_TCT8_22") (pintype "input"))
    )
  )
)
